# adapter-core.net
KiCad netlist of a schematic drawn in Altium Designer
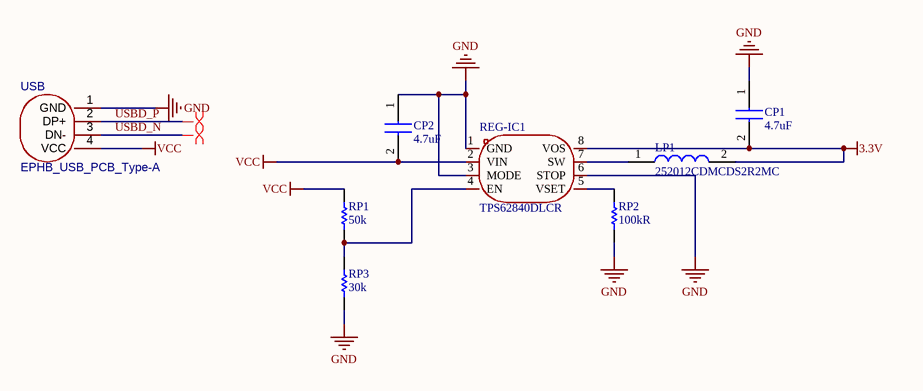
[diagram p0: adapter-core.SchDoc]

(export (version "E")
  (design (tool "Eeschema 10.0.6"))
  (components
    (comp (ref "CP1")
      (value "4.7uF")
      (footprint "CAPC1608X87N")
      (description "Capacitor")
      (fields (field (name "MANUFACTURER_PART_NUMBER") "C0603C100D5GACTU"))
      (libsource (lib "ApexNubLib") (part "C0603C100D5GACTU"))
    )
    (comp (ref "CP2")
      (value "4.7uF")
      (footprint "CAPC1608X87N")
      (description "Capacitor")
      (fields (field (name "MANUFACTURER_PART_NUMBER") "C0603C100D5GACTU"))
      (libsource (lib "ApexNubLib") (part "C0603C100D5GACTU"))
    )
    (comp (ref "LP1")
      (value "252012CDMCDS2R2MC")
      (footprint "INDPM2520X120N")
      (description "Inductor")
      (fields (field (name "MANUFACTURER_PART_NUMBER") "252012CDMCDS‐2R2MC"))
      (libsource (lib "DeskMateLib") (part "252012CDMCDS2R2MC"))
    )
    (comp (ref "REG-IC1")
      (value "TPS62840DLCR")
      (footprint "VSON-8_L2.0-W1.5-P0.50-BL")
      (fields (field (name "MANUFACTURER") "TI(德州仪器)"))
      (libsource (lib "ApexNubLib") (part "TPS62840DLCR"))
    )
    (comp (ref "RP1")
      (value "50k")
      (footprint "RESC1005X40X25LL05T05")
      (description "Chip Resistor, 4.7 KOhm, +/- 1%, 0.1 W, -55 to 155 degC, 0402 (1005 Metric), RoHS, Tape and Reel")
      (fields (field (name "TOLERANCE") "1%") (field (name "PARTNUMBER") "ERJ-2RKF4701X"))
      (libsource (lib "RARM 28 Drive Node") (part "CMP-2002-01154-4"))
    )
    (comp (ref "RP2")
      (value "100kR")
      (footprint "RESC1005X40X25LL05T05")
      (description "Chip Resistor, 4.7 KOhm, +/- 1%, 0.1 W, -55 to 155 degC, 0402 (1005 Metric), RoHS, Tape and Reel")
      (fields (field (name "TOLERANCE") "1%") (field (name "PARTNUMBER") "ERJ-2RKF4701X"))
      (libsource (lib "RARM 28 Drive Node") (part "CMP-2002-01154-4"))
    )
    (comp (ref "RP3")
      (value "30k")
      (footprint "RESC1005X40X25LL05T05")
      (description "Chip Resistor, 4.7 KOhm, +/- 1%, 0.1 W, -55 to 155 degC, 0402 (1005 Metric), RoHS, Tape and Reel")
      (fields (field (name "TOLERANCE") "1%") (field (name "PARTNUMBER") "ERJ-2RKF4701X"))
      (libsource (lib "RARM 28 Drive Node") (part "CMP-2002-01154-4"))
    )
    (comp (ref "USB")
      (value "EPHB_USB_PCB_Type-A")
      (footprint "USB_PCB_Type-A")
      (description "板载USB-Type-A连接器")
      (libsource (lib "ApexNubLib") (part "EPHB_USB_PCB_Type-A"))
    )
  )
  (nets
    (net (code "1") (name "/USBD_N") (class "Default")
      (node (ref "USB") (pin "3") (pinfunction "DN-_3") (pintype "passive"))
    )
    (net (code "2") (name "/USBD_P") (class "Default")
      (node (ref "USB") (pin "2") (pinfunction "DP+_2") (pintype "passive"))
    )
    (net (code "3") (name "3.3V") (class "Default")
      (node (ref "CP1") (pin "2") (pinfunction "2_2") (pintype "passive"))
      (node (ref "LP1") (pin "2") (pinfunction "2_2") (pintype "passive"))
      (node (ref "REG-IC1") (pin "8") (pinfunction "VOS_8") (pintype "passive"))
    )
    (net (code "4") (name "GND") (class "Default")
      (node (ref "CP1") (pin "1") (pinfunction "1_1") (pintype "passive"))
      (node (ref "CP2") (pin "1") (pinfunction "1_1") (pintype "passive"))
      (node (ref "REG-IC1") (pin "1") (pinfunction "GND_1") (pintype "passive"))
      (node (ref "REG-IC1") (pin "3") (pinfunction "MODE_3") (pintype "passive"))
      (node (ref "REG-IC1") (pin "6") (pinfunction "STOP_6") (pintype "passive"))
      (node (ref "RP2") (pin "1") (pinfunction "1_1") (pintype "passive"))
      (node (ref "RP3") (pin "1") (pinfunction "1_1") (pintype "passive"))
      (node (ref "USB") (pin "1") (pinfunction "GND_1") (pintype "passive"))
    )
    (net (code "5") (name "Net-(REG-IC1-EN)") (class "Default")
      (node (ref "REG-IC1") (pin "4") (pinfunction "EN_4") (pintype "passive"))
      (node (ref "RP1") (pin "2") (pinfunction "2_2") (pintype "passive"))
      (node (ref "RP3") (pin "2") (pinfunction "2_2") (pintype "passive"))
    )
    (net (code "6") (name "Net-(REG-IC1-SW)") (class "Default")
      (node (ref "LP1") (pin "1") (pinfunction "1_1") (pintype "passive"))
      (node (ref "REG-IC1") (pin "7") (pinfunction "SW_7") (pintype "passive"))
    )
    (net (code "7") (name "Net-(REG-IC1-VSET)") (class "Default")
      (node (ref "REG-IC1") (pin "5") (pinfunction "VSET_5") (pintype "passive"))
      (node (ref "RP2") (pin "2") (pinfunction "2_2") (pintype "passive"))
    )
    (net (code "8") (name "VCC") (class "Default")
      (node (ref "CP2") (pin "2") (pinfunction "2_2") (pintype "passive"))
      (node (ref "REG-IC1") (pin "2") (pinfunction "VIN_2") (pintype "passive"))
      (node (ref "RP1") (pin "1") (pinfunction "1_1") (pintype "passive"))
      (node (ref "USB") (pin "4") (pinfunction "VCC_4") (pintype "passive"))
    )
  )
)
